# sumoutputpanel.net
KiCad netlist of a schematic drawn in EAGLE
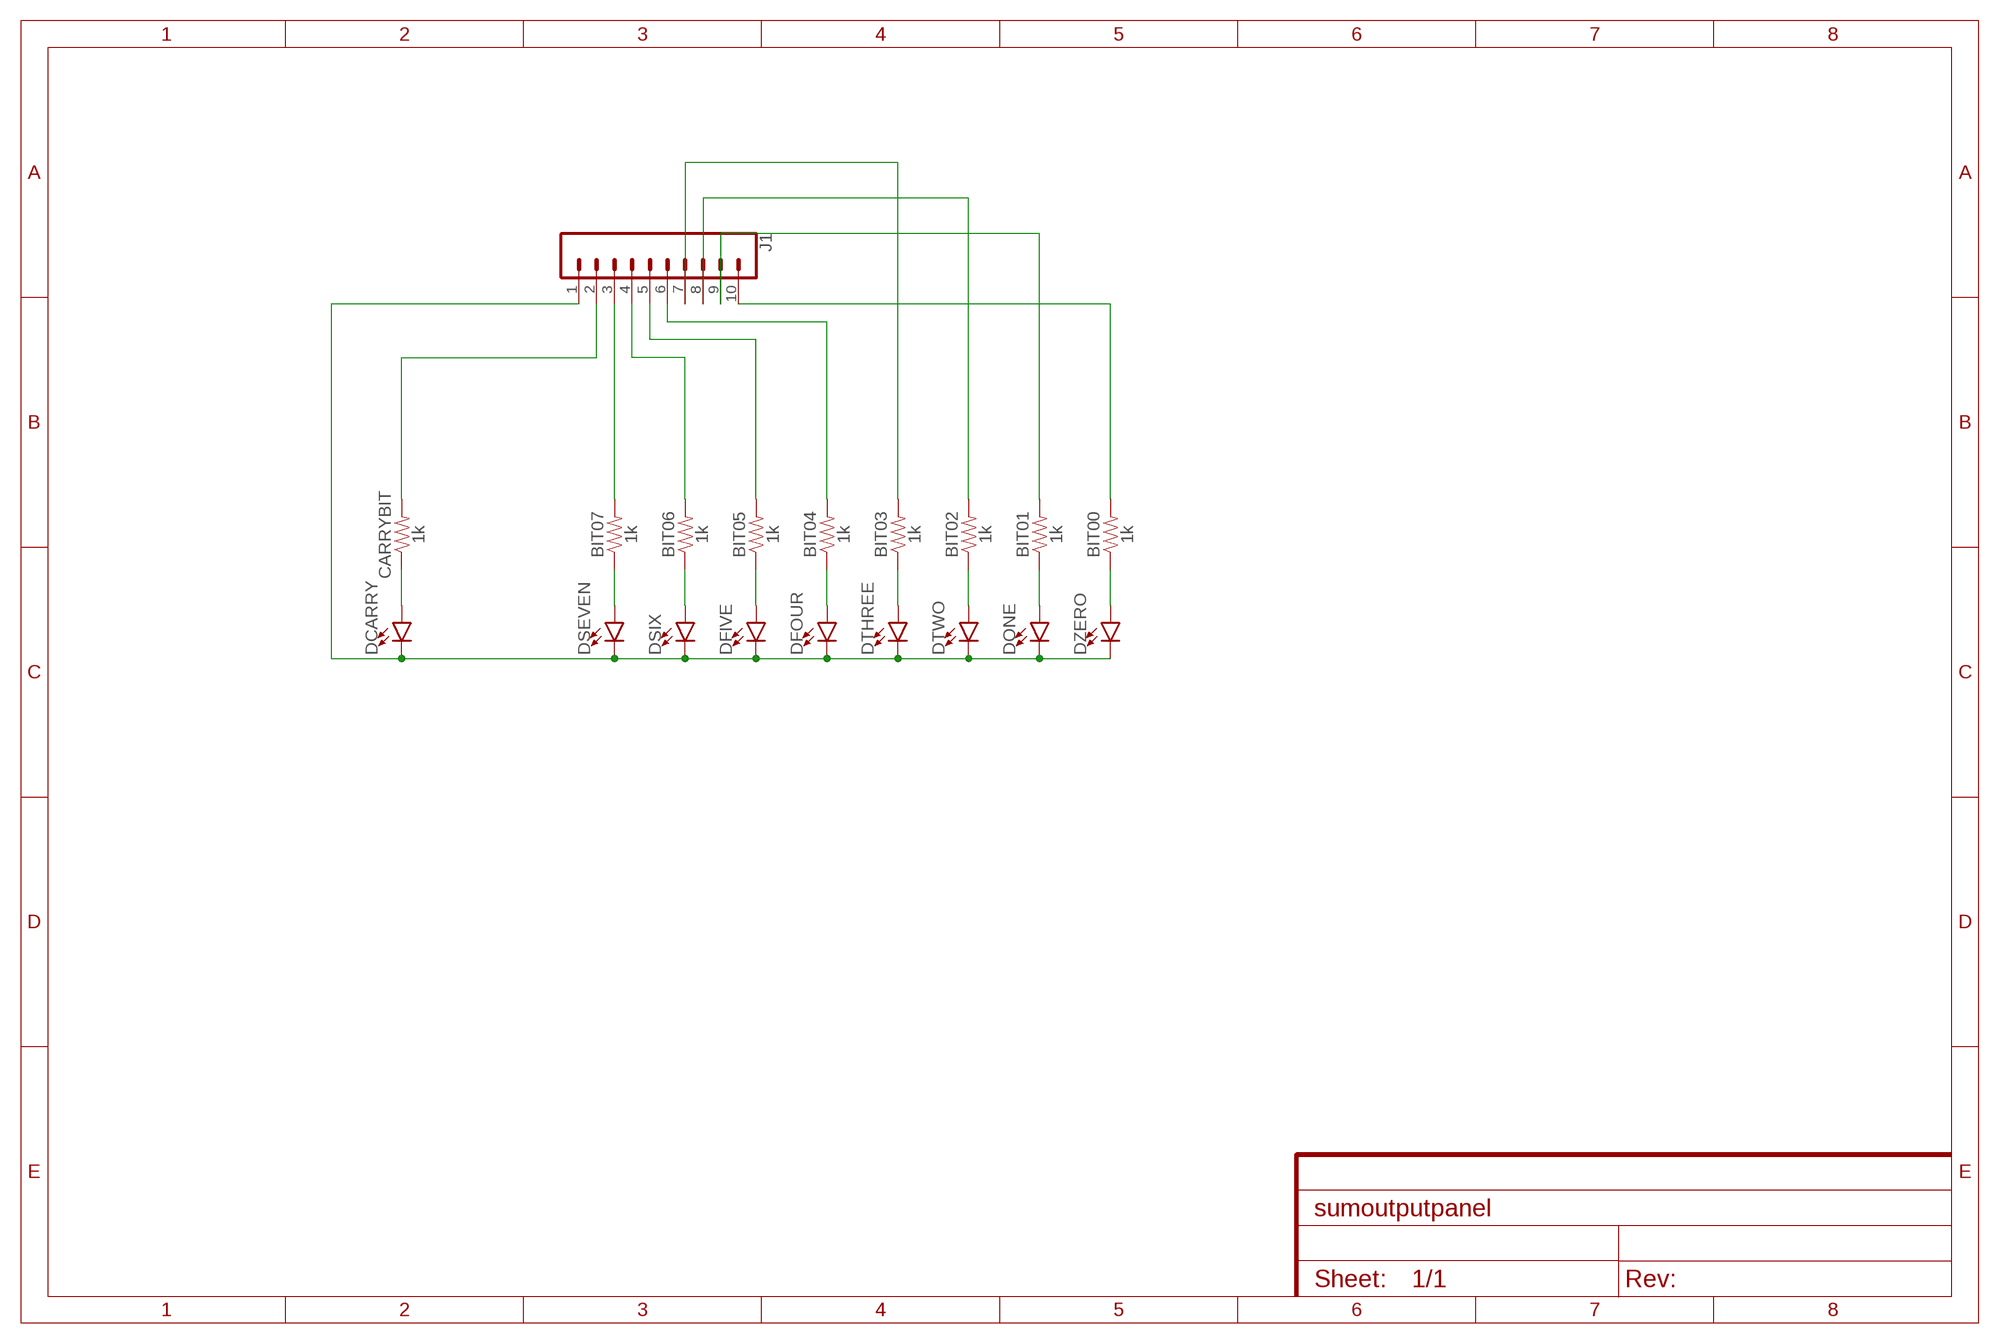
[diagram p0: schematic, sheet 1]

(export (version "E")
  (design (tool "Eeschema 10.0.6"))
  (components
    (comp (ref "BIT00")
      (value "1k")
      (footprint "eagle-import:AXIAL-0.3")
      (libsource (lib "eagle-import") (part "1KOHM-HORIZ-1/4W-5%"))
    )
    (comp (ref "BIT01")
      (value "1k")
      (footprint "eagle-import:AXIAL-0.3")
      (libsource (lib "eagle-import") (part "1KOHM-HORIZ-1/4W-5%"))
    )
    (comp (ref "BIT02")
      (value "1k")
      (footprint "eagle-import:AXIAL-0.3")
      (libsource (lib "eagle-import") (part "1KOHM-HORIZ-1/4W-5%"))
    )
    (comp (ref "BIT03")
      (value "1k")
      (footprint "eagle-import:AXIAL-0.3")
      (libsource (lib "eagle-import") (part "1KOHM-HORIZ-1/4W-5%"))
    )
    (comp (ref "BIT04")
      (value "1k")
      (footprint "eagle-import:AXIAL-0.3")
      (libsource (lib "eagle-import") (part "1KOHM-HORIZ-1/4W-5%"))
    )
    (comp (ref "BIT05")
      (value "1k")
      (footprint "eagle-import:AXIAL-0.3")
      (libsource (lib "eagle-import") (part "1KOHM-HORIZ-1/4W-5%"))
    )
    (comp (ref "BIT06")
      (value "1k")
      (footprint "eagle-import:AXIAL-0.3")
      (libsource (lib "eagle-import") (part "1KOHM-HORIZ-1/4W-5%"))
    )
    (comp (ref "BIT07")
      (value "1k")
      (footprint "eagle-import:AXIAL-0.3")
      (libsource (lib "eagle-import") (part "1KOHM-HORIZ-1/4W-5%"))
    )
    (comp (ref "CARRYBIT")
      (value "1k")
      (footprint "eagle-import:AXIAL-0.3")
      (libsource (lib "eagle-import") (part "1KOHM-HORIZ-1/4W-5%"))
    )
    (comp (ref "DCARRY")
      (value "LED5MM")
      (footprint "eagle-import:LED_5MM")
      (libsource (lib "eagle-import") (part "LED5MM"))
    )
    (comp (ref "DFIVE")
      (value "LED5MM")
      (footprint "eagle-import:LED_5MM")
      (libsource (lib "eagle-import") (part "LED5MM"))
    )
    (comp (ref "DFOUR")
      (value "LED5MM")
      (footprint "eagle-import:LED_5MM")
      (libsource (lib "eagle-import") (part "LED5MM"))
    )
    (comp (ref "DONE")
      (value "LED5MM")
      (footprint "eagle-import:LED_5MM")
      (libsource (lib "eagle-import") (part "LED5MM"))
    )
    (comp (ref "DSEVEN")
      (value "LED5MM")
      (footprint "eagle-import:LED_5MM")
      (libsource (lib "eagle-import") (part "LED5MM"))
    )
    (comp (ref "DSIX")
      (value "LED5MM")
      (footprint "eagle-import:LED_5MM")
      (libsource (lib "eagle-import") (part "LED5MM"))
    )
    (comp (ref "DTHREE")
      (value "LED5MM")
      (footprint "eagle-import:LED_5MM")
      (libsource (lib "eagle-import") (part "LED5MM"))
    )
    (comp (ref "DTWO")
      (value "LED5MM")
      (footprint "eagle-import:LED_5MM")
      (libsource (lib "eagle-import") (part "LED5MM"))
    )
    (comp (ref "DZERO")
      (value "LED5MM")
      (footprint "eagle-import:LED_5MM")
      (libsource (lib "eagle-import") (part "LED5MM"))
    )
    (comp (ref "J1")
      (value "CONN_10\"")
      (footprint "eagle-import:1X10")
      (libsource (lib "eagle-import") (part "CONN_10{dblquote}"))
    )
  )
  (nets
    (net (code "1") (name "Net-(BIT00-1)") (class "Default")
      (node (ref "BIT00") (pin "P$1") (pinfunction "1_P$1") (pintype "passive"))
      (node (ref "DZERO") (pin "A") (pinfunction "A_A") (pintype "passive"))
    )
    (net (code "2") (name "Net-(BIT00-2)") (class "Default")
      (node (ref "BIT00") (pin "P$2") (pinfunction "2_P$2") (pintype "passive"))
      (node (ref "J1") (pin "10") (pinfunction "10_10") (pintype "passive"))
    )
    (net (code "3") (name "Net-(BIT01-1)") (class "Default")
      (node (ref "BIT01") (pin "P$1") (pinfunction "1_P$1") (pintype "passive"))
      (node (ref "DONE") (pin "A") (pinfunction "A_A") (pintype "passive"))
    )
    (net (code "4") (name "Net-(BIT01-2)") (class "Default")
      (node (ref "BIT01") (pin "P$2") (pinfunction "2_P$2") (pintype "passive"))
      (node (ref "J1") (pin "9") (pinfunction "9_9") (pintype "passive"))
    )
    (net (code "5") (name "Net-(BIT02-1)") (class "Default")
      (node (ref "BIT02") (pin "P$1") (pinfunction "1_P$1") (pintype "passive"))
      (node (ref "DTWO") (pin "A") (pinfunction "A_A") (pintype "passive"))
    )
    (net (code "6") (name "Net-(BIT02-2)") (class "Default")
      (node (ref "BIT02") (pin "P$2") (pinfunction "2_P$2") (pintype "passive"))
      (node (ref "J1") (pin "8") (pinfunction "8_8") (pintype "passive"))
    )
    (net (code "7") (name "Net-(BIT03-1)") (class "Default")
      (node (ref "BIT03") (pin "P$1") (pinfunction "1_P$1") (pintype "passive"))
      (node (ref "DTHREE") (pin "A") (pinfunction "A_A") (pintype "passive"))
    )
    (net (code "8") (name "Net-(BIT03-2)") (class "Default")
      (node (ref "BIT03") (pin "P$2") (pinfunction "2_P$2") (pintype "passive"))
      (node (ref "J1") (pin "7") (pinfunction "7_7") (pintype "passive"))
    )
    (net (code "9") (name "Net-(BIT04-1)") (class "Default")
      (node (ref "BIT04") (pin "P$1") (pinfunction "1_P$1") (pintype "passive"))
      (node (ref "DFOUR") (pin "A") (pinfunction "A_A") (pintype "passive"))
    )
    (net (code "10") (name "Net-(BIT04-2)") (class "Default")
      (node (ref "BIT04") (pin "P$2") (pinfunction "2_P$2") (pintype "passive"))
      (node (ref "J1") (pin "6") (pinfunction "6_6") (pintype "passive"))
    )
    (net (code "11") (name "Net-(BIT05-1)") (class "Default")
      (node (ref "BIT05") (pin "P$1") (pinfunction "1_P$1") (pintype "passive"))
      (node (ref "DFIVE") (pin "A") (pinfunction "A_A") (pintype "passive"))
    )
    (net (code "12") (name "Net-(BIT05-2)") (class "Default")
      (node (ref "BIT05") (pin "P$2") (pinfunction "2_P$2") (pintype "passive"))
      (node (ref "J1") (pin "5") (pinfunction "5_5") (pintype "passive"))
    )
    (net (code "13") (name "Net-(BIT06-1)") (class "Default")
      (node (ref "BIT06") (pin "P$1") (pinfunction "1_P$1") (pintype "passive"))
      (node (ref "DSIX") (pin "A") (pinfunction "A_A") (pintype "passive"))
    )
    (net (code "14") (name "Net-(BIT06-2)") (class "Default")
      (node (ref "BIT06") (pin "P$2") (pinfunction "2_P$2") (pintype "passive"))
      (node (ref "J1") (pin "4") (pinfunction "4_4") (pintype "passive"))
    )
    (net (code "15") (name "Net-(BIT07-1)") (class "Default")
      (node (ref "BIT07") (pin "P$1") (pinfunction "1_P$1") (pintype "passive"))
      (node (ref "DSEVEN") (pin "A") (pinfunction "A_A") (pintype "passive"))
    )
    (net (code "16") (name "Net-(BIT07-2)") (class "Default")
      (node (ref "BIT07") (pin "P$2") (pinfunction "2_P$2") (pintype "passive"))
      (node (ref "J1") (pin "3") (pinfunction "3_3") (pintype "passive"))
    )
    (net (code "17") (name "Net-(CARRYBIT-1)") (class "Default")
      (node (ref "CARRYBIT") (pin "P$1") (pinfunction "1_P$1") (pintype "passive"))
      (node (ref "DCARRY") (pin "A") (pinfunction "A_A") (pintype "passive"))
    )
    (net (code "18") (name "Net-(CARRYBIT-2)") (class "Default")
      (node (ref "CARRYBIT") (pin "P$2") (pinfunction "2_P$2") (pintype "passive"))
      (node (ref "J1") (pin "2") (pinfunction "2_2") (pintype "passive"))
    )
    (net (code "19") (name "Net-(DCARRY-C)") (class "Default")
      (node (ref "DCARRY") (pin "K") (pinfunction "C_K") (pintype "passive"))
      (node (ref "DFIVE") (pin "K") (pinfunction "C_K") (pintype "passive"))
      (node (ref "DFOUR") (pin "K") (pinfunction "C_K") (pintype "passive"))
      (node (ref "DONE") (pin "K") (pinfunction "C_K") (pintype "passive"))
      (node (ref "DSEVEN") (pin "K") (pinfunction "C_K") (pintype "passive"))
      (node (ref "DSIX") (pin "K") (pinfunction "C_K") (pintype "passive"))
      (node (ref "DTHREE") (pin "K") (pinfunction "C_K") (pintype "passive"))
      (node (ref "DTWO") (pin "K") (pinfunction "C_K") (pintype "passive"))
      (node (ref "DZERO") (pin "K") (pinfunction "C_K") (pintype "passive"))
      (node (ref "J1") (pin "1") (pinfunction "1_1") (pintype "passive"))
    )
  )
)
